# Sheet1.net
KiCad netlist of a schematic drawn in Altium Designer
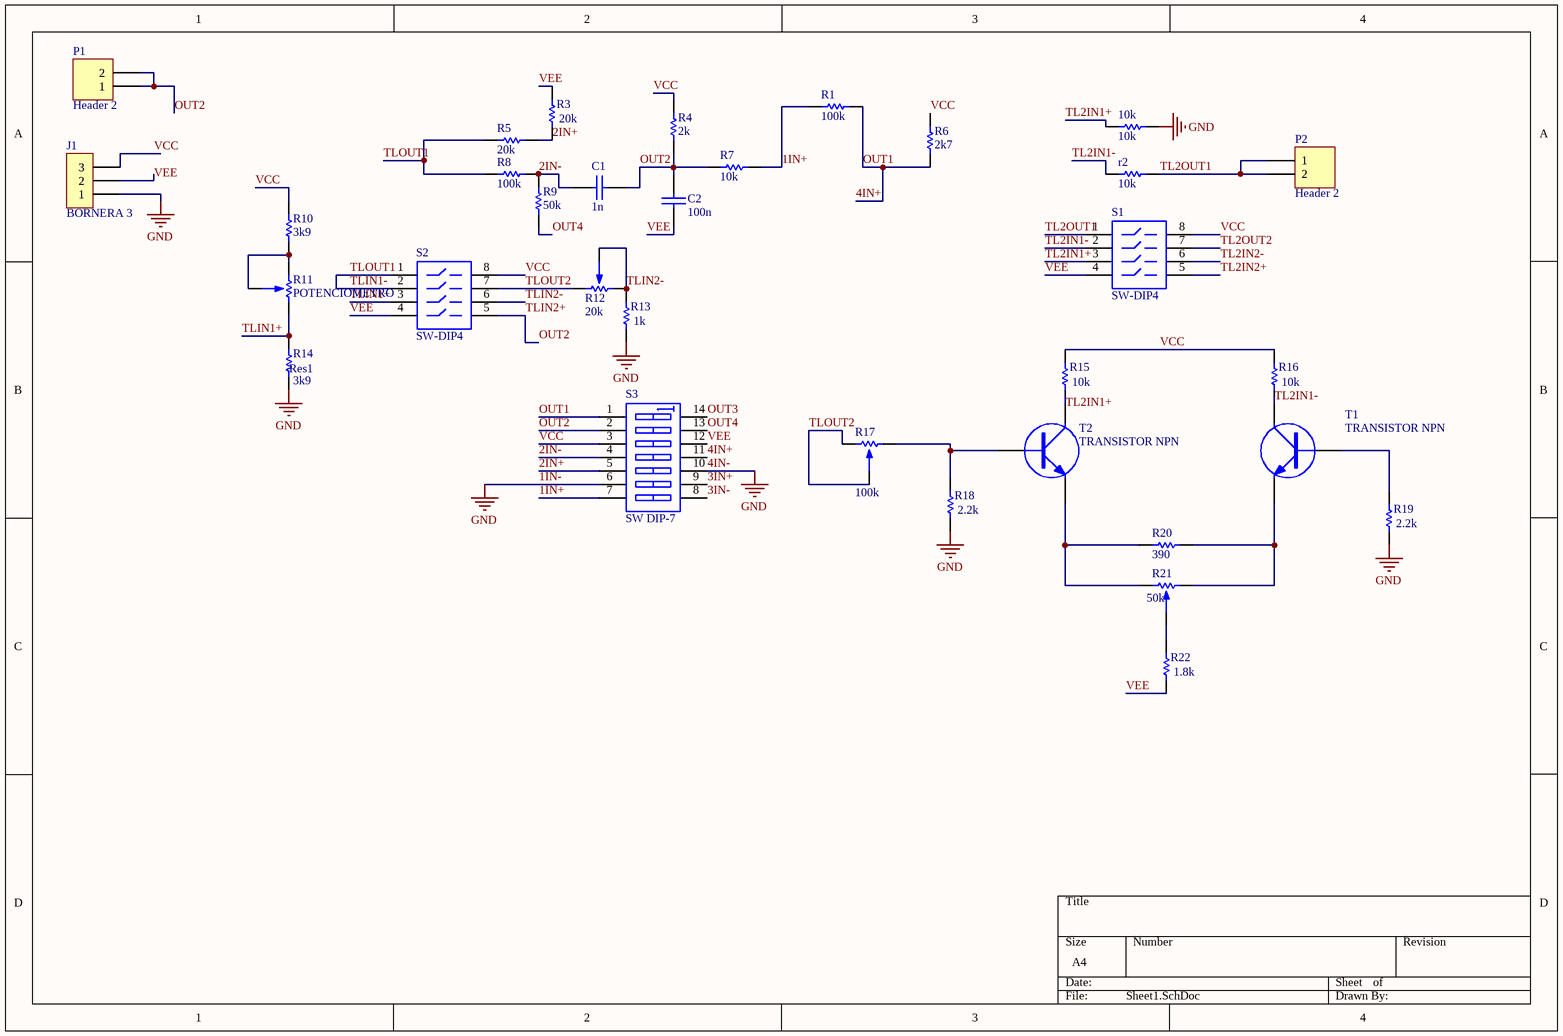
[diagram p0: Sheet1.SchDoc]

(export (version "E")
  (design (tool "Eeschema 10.0.6"))
  (components
    (comp (ref "10k") (value "10k") (footprint "RES600") (libsource (lib "LIBEBAL") (part "RES")))
    (comp (ref "C1") (value "1n") (footprint "CAP200") (libsource (lib "LIBEBAL") (part "CAP")))
    (comp (ref "C2") (value "100n") (footprint "CAP200") (libsource (lib "LIBEBAL") (part "CAP")))
    (comp (ref "J1")
      (value "BORNERA 3")
      (footprint "BORNERA3")
      (libsource (lib "LIBEBAL") (part "BORNERA 3"))
    )
    (comp (ref "P1")
      (value "Header 2")
      (footprint "HDR1X2")
      (description "Header, 2-Pin")
      (fields (field (name "PUBLISHER") "Altium Limited"))
      (libsource (lib "") (part "Header 2_1"))
    )
    (comp (ref "P2")
      (value "Header 2")
      (footprint "HDR1X2")
      (description "Header, 2-Pin")
      (fields (field (name "PUBLISHER") "Altium Limited"))
      (libsource (lib "Miscellaneous Connectors") (part "Header 2"))
    )
    (comp (ref "R1") (value "100k") (footprint "RES600") (libsource (lib "LIBEBAL") (part "RES")))
    (comp (ref "r2") (value "10k") (footprint "RES600") (libsource (lib "LIBEBAL") (part "RES")))
    (comp (ref "R3") (value "20k") (footprint "RES600") (libsource (lib "LIBEBAL") (part "RES")))
    (comp (ref "R4") (value "2k") (footprint "RES600") (libsource (lib "LIBEBAL") (part "RES")))
    (comp (ref "R5") (value "20k") (footprint "RES600") (libsource (lib "LIBEBAL") (part "RES")))
    (comp (ref "R6") (value "2k7") (footprint "RES600") (libsource (lib "LIBEBAL") (part "RES")))
    (comp (ref "R7") (value "10k") (footprint "RES600") (libsource (lib "LIBEBAL") (part "RES")))
    (comp (ref "R8") (value "100k") (footprint "RES600") (libsource (lib "LIBEBAL") (part "RES")))
    (comp (ref "R9") (value "50k") (footprint "RES600") (libsource (lib "LIBEBAL") (part "RES")))
    (comp (ref "R10") (value "3k9") (footprint "RES600") (libsource (lib "LIBEBAL") (part "RES")))
    (comp (ref "R11")
      (value "POTENCIOMETRO")
      (footprint "POTENCIOMETRO")
      (libsource (lib "LIBEBAL") (part "POTENCIOMETRO"))
    )
    (comp (ref "R12") (value "20k") (footprint "PRESET V") (libsource (lib "LIBEBAL") (part "PRESET")))
    (comp (ref "R13") (value "1k") (footprint "RES600") (libsource (lib "LIBEBAL") (part "RES")))
    (comp (ref "R14")
      (value "Res1")
      (footprint "AXIAL-0.3")
      (description "Resistor")
      (fields (field (name "ALTIUM_VALUE") "3k9") (field (name "PUBLISHER") "Altium Limited"))
      (libsource (lib "Miscellaneous Devices") (part "Res1"))
    )
    (comp (ref "R15") (value "10k") (footprint "RES600") (libsource (lib "LIBEBAL") (part "RES")))
    (comp (ref "R16") (value "10k") (footprint "RES600") (libsource (lib "LIBEBAL") (part "RES")))
    (comp (ref "R17") (value "100k") (footprint "PRESET V") (libsource (lib "LIBEBAL") (part "PRESET")))
    (comp (ref "R18") (value "2.2k") (footprint "RES600") (libsource (lib "LIBEBAL") (part "RES")))
    (comp (ref "R19") (value "2.2k") (footprint "RES600") (libsource (lib "LIBEBAL") (part "RES")))
    (comp (ref "R20") (value "390") (footprint "RES600") (libsource (lib "LIBEBAL") (part "RES")))
    (comp (ref "R21") (value "50k") (footprint "PRESET V") (libsource (lib "LIBEBAL") (part "PRESET")))
    (comp (ref "R22") (value "1.8k") (footprint "RES600") (libsource (lib "LIBEBAL") (part "RES")))
    (comp (ref "S1")
      (value "SW-DIP4")
      (footprint "DIP-8")
      (description "DIP Switch")
      (fields (field (name "PUBLISHER") "Altium Limited"))
      (libsource (lib "Miscellaneous Devices") (part "SW-DIP4"))
    )
    (comp (ref "S2")
      (value "SW-DIP4")
      (footprint "DIP-8")
      (description "DIP Switch")
      (fields (field (name "PUBLISHER") "Altium Limited"))
      (libsource (lib "Miscellaneous Devices") (part "SW-DIP4"))
    )
    (comp (ref "S3")
      (value "SW DIP-7")
      (footprint "DIP-14")
      (description "DIP Switch, 7 Position, SPST")
      (fields (field (name "PUBLISHER") "Altium Limited"))
      (libsource (lib "Miscellaneous Devices") (part "SW DIP-7"))
    )
    (comp (ref "T1")
      (value "TRANSISTOR NPN")
      (footprint "TO92")
      (libsource (lib "LIBEBAL") (part "TRANSISTOR NPN"))
    )
    (comp (ref "T2")
      (value "TRANSISTOR NPN")
      (footprint "TO92")
      (libsource (lib "LIBEBAL") (part "TRANSISTOR NPN"))
    )
  )
  (nets
    (net (code "1") (name "/1IN+") (class "Default")
      (node (ref "R1") (pin "2") (pinfunction "2_2") (pintype "passive"))
      (node (ref "R7") (pin "1") (pinfunction "1_1") (pintype "passive"))
      (node (ref "S3") (pin "7") (pinfunction "A7_7") (pintype "passive"))
    )
    (net (code "2") (name "/2IN+") (class "Default")
      (node (ref "R3") (pin "1") (pinfunction "1_1") (pintype "passive"))
      (node (ref "R5") (pin "2") (pinfunction "2_2") (pintype "passive"))
      (node (ref "S3") (pin "5") (pinfunction "A5_5") (pintype "passive"))
    )
    (net (code "3") (name "/2IN-") (class "Default")
      (node (ref "C1") (pin "1") (pinfunction "1_1") (pintype "passive"))
      (node (ref "R8") (pin "2") (pinfunction "2_2") (pintype "passive"))
      (node (ref "R9") (pin "2") (pinfunction "2_2") (pintype "passive"))
      (node (ref "S3") (pin "4") (pinfunction "A4_4") (pintype "passive"))
    )
    (net (code "4") (name "/3IN+") (class "Default")
      (node (ref "S3") (pin "9") (pinfunction "B6_9") (pintype "passive"))
    )
    (net (code "5") (name "/3IN-") (class "Default")
      (node (ref "S3") (pin "8") (pinfunction "B7_8") (pintype "passive"))
    )
    (net (code "6") (name "/4IN+") (class "Default")
      (node (ref "R1") (pin "1") (pinfunction "1_1") (pintype "passive"))
      (node (ref "R6") (pin "2") (pinfunction "2_2") (pintype "passive"))
      (node (ref "S3") (pin "1") (pinfunction "A1_1") (pintype "passive"))
      (node (ref "S3") (pin "11") (pinfunction "B4_11") (pintype "passive"))
    )
    (net (code "7") (name "/OUT2") (class "Default")
      (node (ref "C1") (pin "2") (pinfunction "2_2") (pintype "passive"))
      (node (ref "C2") (pin "2") (pinfunction "2_2") (pintype "passive"))
      (node (ref "P1") (pin "1") (pinfunction "1_1") (pintype "passive"))
      (node (ref "P1") (pin "2") (pinfunction "2_2") (pintype "passive"))
      (node (ref "R4") (pin "1") (pinfunction "1_1") (pintype "passive"))
      (node (ref "R7") (pin "2") (pinfunction "2_2") (pintype "passive"))
      (node (ref "S2") (pin "5") (pinfunction "5_5") (pintype "passive"))
      (node (ref "S3") (pin "2") (pinfunction "A2_2") (pintype "passive"))
    )
    (net (code "8") (name "/OUT3") (class "Default")
      (node (ref "S3") (pin "14") (pinfunction "B1_14") (pintype "passive"))
    )
    (net (code "9") (name "/OUT4") (class "Default")
      (node (ref "R9") (pin "1") (pinfunction "1_1") (pintype "passive"))
      (node (ref "S3") (pin "13") (pinfunction "B2_13") (pintype "passive"))
    )
    (net (code "10") (name "/TL2IN1+") (class "Default")
      (node (ref "10k") (pin "1") (pinfunction "1_1") (pintype "passive"))
      (node (ref "S1") (pin "3") (pinfunction "3_3") (pintype "passive"))
    )
    (net (code "11") (name "/TL2IN1-") (class "Default")
      (node (ref "R16") (pin "2") (pinfunction "2_2") (pintype "passive"))
      (node (ref "S1") (pin "2") (pinfunction "2_2") (pintype "passive"))
      (node (ref "T1") (pin "2") (pinfunction "C_2") (pintype "passive"))
      (node (ref "r2") (pin "1") (pinfunction "1_1") (pintype "passive"))
    )
    (net (code "12") (name "/TL2IN2+") (class "Default")
      (node (ref "S1") (pin "5") (pinfunction "5_5") (pintype "passive"))
    )
    (net (code "13") (name "/TL2IN2-") (class "Default")
      (node (ref "S1") (pin "6") (pinfunction "6_6") (pintype "passive"))
    )
    (net (code "14") (name "/TL2OUT1") (class "Default")
      (node (ref "P2") (pin "1") (pinfunction "1_1") (pintype "passive"))
      (node (ref "P2") (pin "2") (pinfunction "2_2") (pintype "passive"))
      (node (ref "S1") (pin "1") (pinfunction "1_1") (pintype "passive"))
      (node (ref "r2") (pin "2") (pinfunction "2_2") (pintype "passive"))
    )
    (net (code "15") (name "/TL2OUT2") (class "Default")
      (node (ref "S1") (pin "7") (pinfunction "7_7") (pintype "passive"))
    )
    (net (code "16") (name "/TLIN1+") (class "Default")
      (node (ref "R11") (pin "1") (pinfunction "1_1") (pintype "passive"))
      (node (ref "R14") (pin "2") (pinfunction "2_2") (pintype "passive"))
      (node (ref "S2") (pin "3") (pinfunction "3_3") (pintype "passive"))
    )
    (net (code "17") (name "/TLIN1-") (class "Default")
      (node (ref "R5") (pin "1") (pinfunction "1_1") (pintype "passive"))
      (node (ref "R8") (pin "1") (pinfunction "1_1") (pintype "passive"))
      (node (ref "S2") (pin "1") (pinfunction "1_1") (pintype "passive"))
      (node (ref "S2") (pin "2") (pinfunction "2_2") (pintype "passive"))
    )
    (net (code "18") (name "/TLIN2-") (class "Default")
      (node (ref "R12") (pin "2") (pinfunction "2_2") (pintype "passive"))
      (node (ref "R12") (pin "3") (pinfunction "3_3") (pintype "passive"))
      (node (ref "R13") (pin "1") (pinfunction "1_1") (pintype "passive"))
      (node (ref "S2") (pin "6") (pinfunction "6_6") (pintype "passive"))
    )
    (net (code "19") (name "/TLOUT2") (class "Default")
      (node (ref "R12") (pin "1") (pinfunction "1_1") (pintype "passive"))
      (node (ref "R17") (pin "2") (pinfunction "2_2") (pintype "passive"))
      (node (ref "R17") (pin "3") (pinfunction "3_3") (pintype "passive"))
      (node (ref "S2") (pin "7") (pinfunction "7_7") (pintype "passive"))
    )
    (net (code "20") (name "/VCC") (class "Default")
      (node (ref "J1") (pin "3") (pinfunction "3_3") (pintype "passive"))
      (node (ref "R10") (pin "2") (pinfunction "2_2") (pintype "passive"))
      (node (ref "R15") (pin "1") (pinfunction "1_1") (pintype "passive"))
      (node (ref "R16") (pin "1") (pinfunction "1_1") (pintype "passive"))
      (node (ref "R4") (pin "2") (pinfunction "2_2") (pintype "passive"))
      (node (ref "R6") (pin "1") (pinfunction "1_1") (pintype "passive"))
      (node (ref "S1") (pin "8") (pinfunction "8_8") (pintype "passive"))
      (node (ref "S2") (pin "8") (pinfunction "8_8") (pintype "passive"))
      (node (ref "S3") (pin "3") (pinfunction "A3_3") (pintype "passive"))
    )
    (net (code "21") (name "/VEE") (class "Default")
      (node (ref "C2") (pin "1") (pinfunction "1_1") (pintype "passive"))
      (node (ref "J1") (pin "2") (pinfunction "2_2") (pintype "passive"))
      (node (ref "R22") (pin "2") (pinfunction "2_2") (pintype "passive"))
      (node (ref "R3") (pin "2") (pinfunction "2_2") (pintype "passive"))
      (node (ref "S1") (pin "4") (pinfunction "4_4") (pintype "passive"))
      (node (ref "S2") (pin "4") (pinfunction "4_4") (pintype "passive"))
      (node (ref "S3") (pin "12") (pinfunction "B3_12") (pintype "passive"))
    )
    (net (code "22") (name "GND") (class "Default")
      (node (ref "10k") (pin "2") (pinfunction "2_2") (pintype "passive"))
      (node (ref "J1") (pin "1") (pinfunction "1_1") (pintype "passive"))
      (node (ref "R13") (pin "2") (pinfunction "2_2") (pintype "passive"))
      (node (ref "R14") (pin "1") (pinfunction "1_1") (pintype "passive"))
      (node (ref "R18") (pin "2") (pinfunction "2_2") (pintype "passive"))
      (node (ref "R19") (pin "2") (pinfunction "2_2") (pintype "passive"))
      (node (ref "S3") (pin "10") (pinfunction "B5_10") (pintype "passive"))
      (node (ref "S3") (pin "6") (pinfunction "A6_6") (pintype "passive"))
    )
    (net (code "23") (name "Net-(R10-Pad1)") (class "Default")
      (node (ref "R10") (pin "1") (pinfunction "1_1") (pintype "passive"))
      (node (ref "R11") (pin "2") (pinfunction "2_2") (pintype "passive"))
      (node (ref "R11") (pin "3") (pinfunction "3_3") (pintype "passive"))
    )
    (net (code "24") (name "Net-(R21-Pad2)") (class "Default")
      (node (ref "R21") (pin "2") (pinfunction "2_2") (pintype "passive"))
      (node (ref "R22") (pin "1") (pinfunction "1_1") (pintype "passive"))
    )
    (net (code "25") (name "Net-(T1-B)") (class "Default")
      (node (ref "R19") (pin "1") (pinfunction "1_1") (pintype "passive"))
      (node (ref "T1") (pin "1") (pinfunction "B_1") (pintype "passive"))
    )
    (net (code "26") (name "Net-(T1-E)") (class "Default")
      (node (ref "R20") (pin "1") (pinfunction "1_1") (pintype "passive"))
      (node (ref "R21") (pin "1") (pinfunction "1_1") (pintype "passive"))
      (node (ref "T1") (pin "3") (pinfunction "E_3") (pintype "passive"))
    )
    (net (code "27") (name "Net-(T2-B)") (class "Default")
      (node (ref "R17") (pin "1") (pinfunction "1_1") (pintype "passive"))
      (node (ref "R18") (pin "1") (pinfunction "1_1") (pintype "passive"))
      (node (ref "T2") (pin "1") (pinfunction "B_1") (pintype "passive"))
    )
    (net (code "28") (name "Net-(T2-C)") (class "Default")
      (node (ref "R15") (pin "2") (pinfunction "2_2") (pintype "passive"))
      (node (ref "T2") (pin "2") (pinfunction "C_2") (pintype "passive"))
    )
    (net (code "29") (name "Net-(T2-E)") (class "Default")
      (node (ref "R20") (pin "2") (pinfunction "2_2") (pintype "passive"))
      (node (ref "R21") (pin "3") (pinfunction "3_3") (pintype "passive"))
      (node (ref "T2") (pin "3") (pinfunction "E_3") (pintype "passive"))
    )
  )
)
